# GPRS-Shield-v3_0.net
KiCad netlist of a schematic drawn in EAGLE
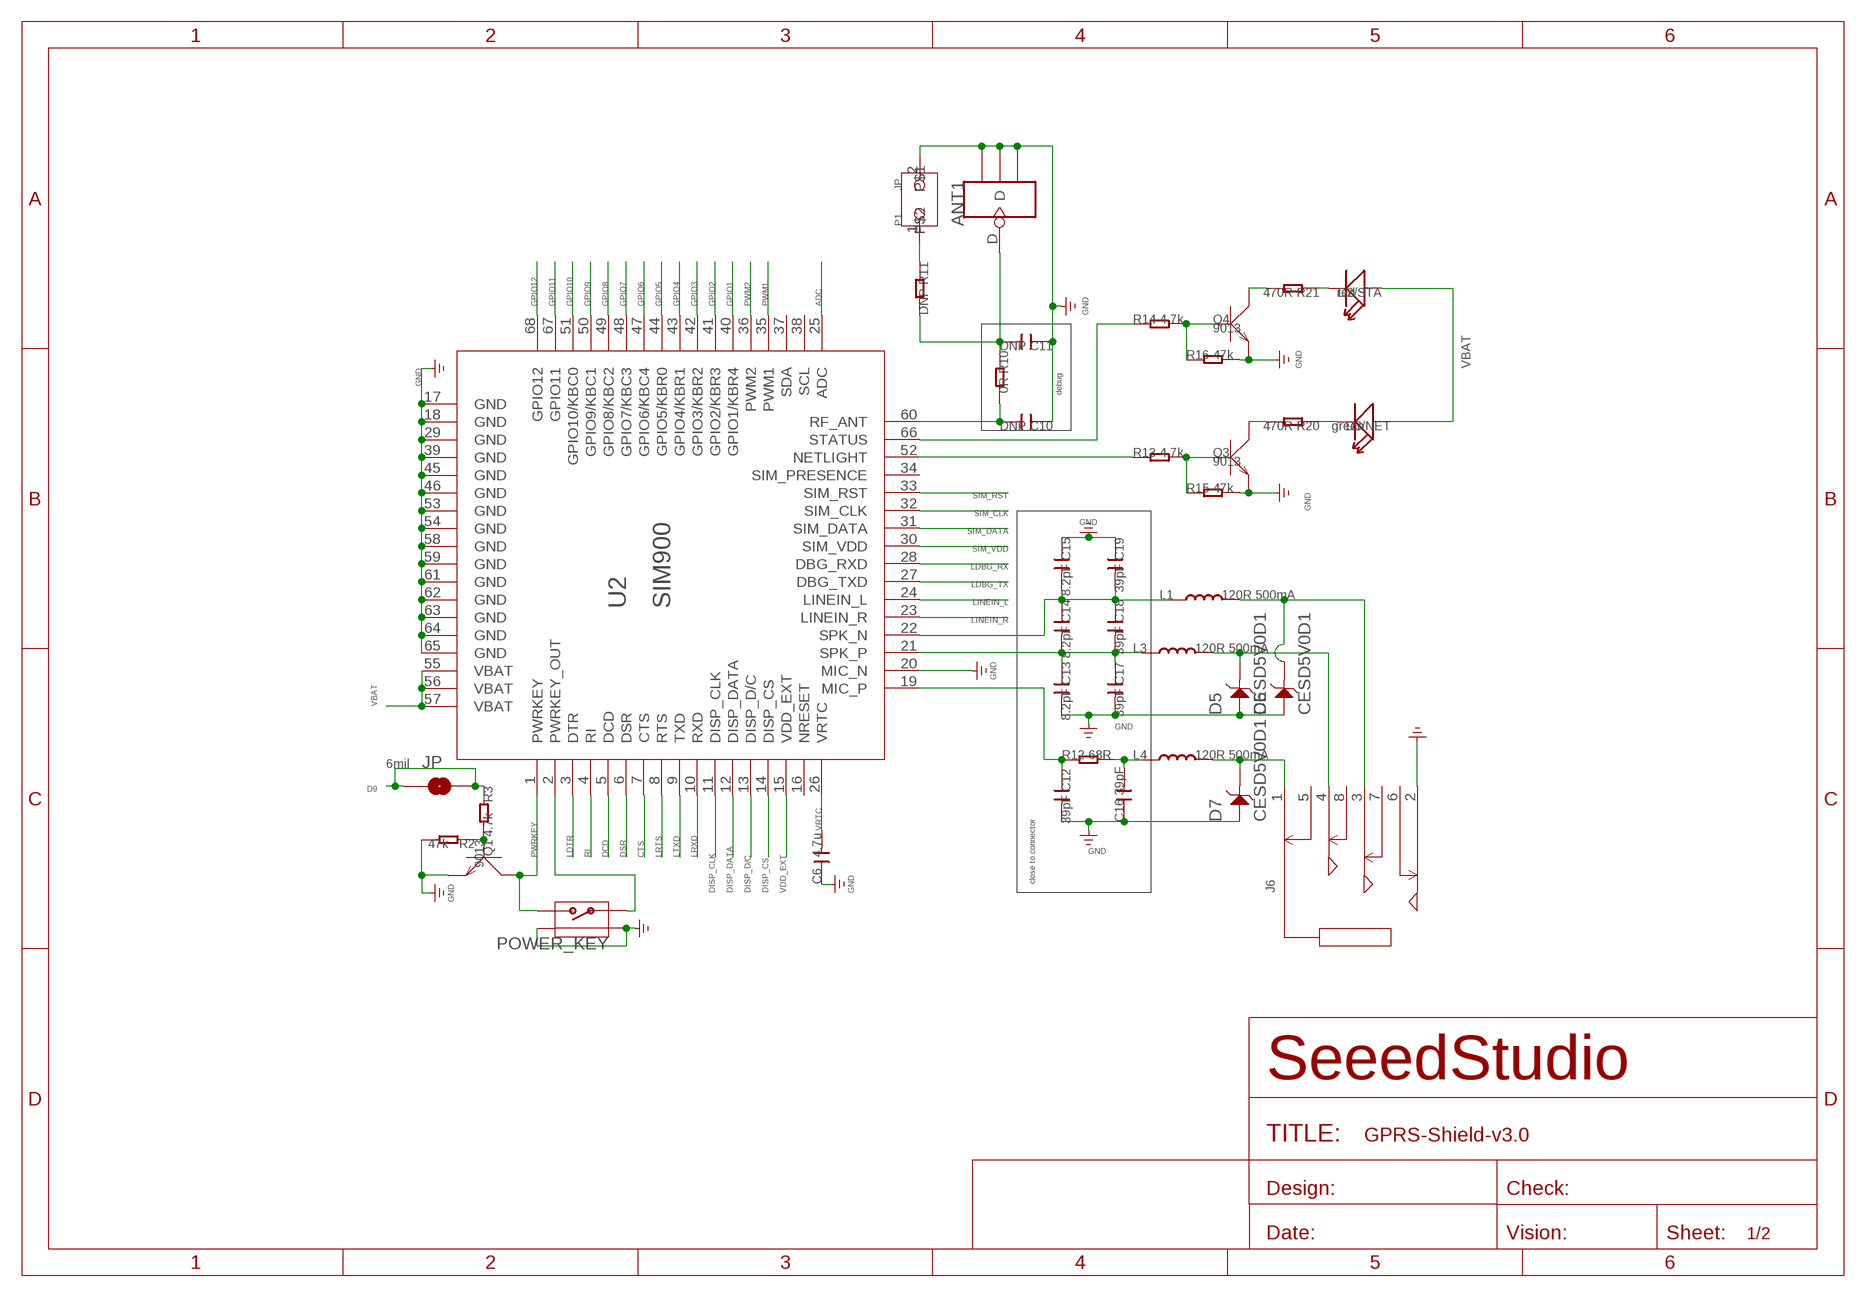
[diagram p0: schematic, sheet 1, part 1 of 2]
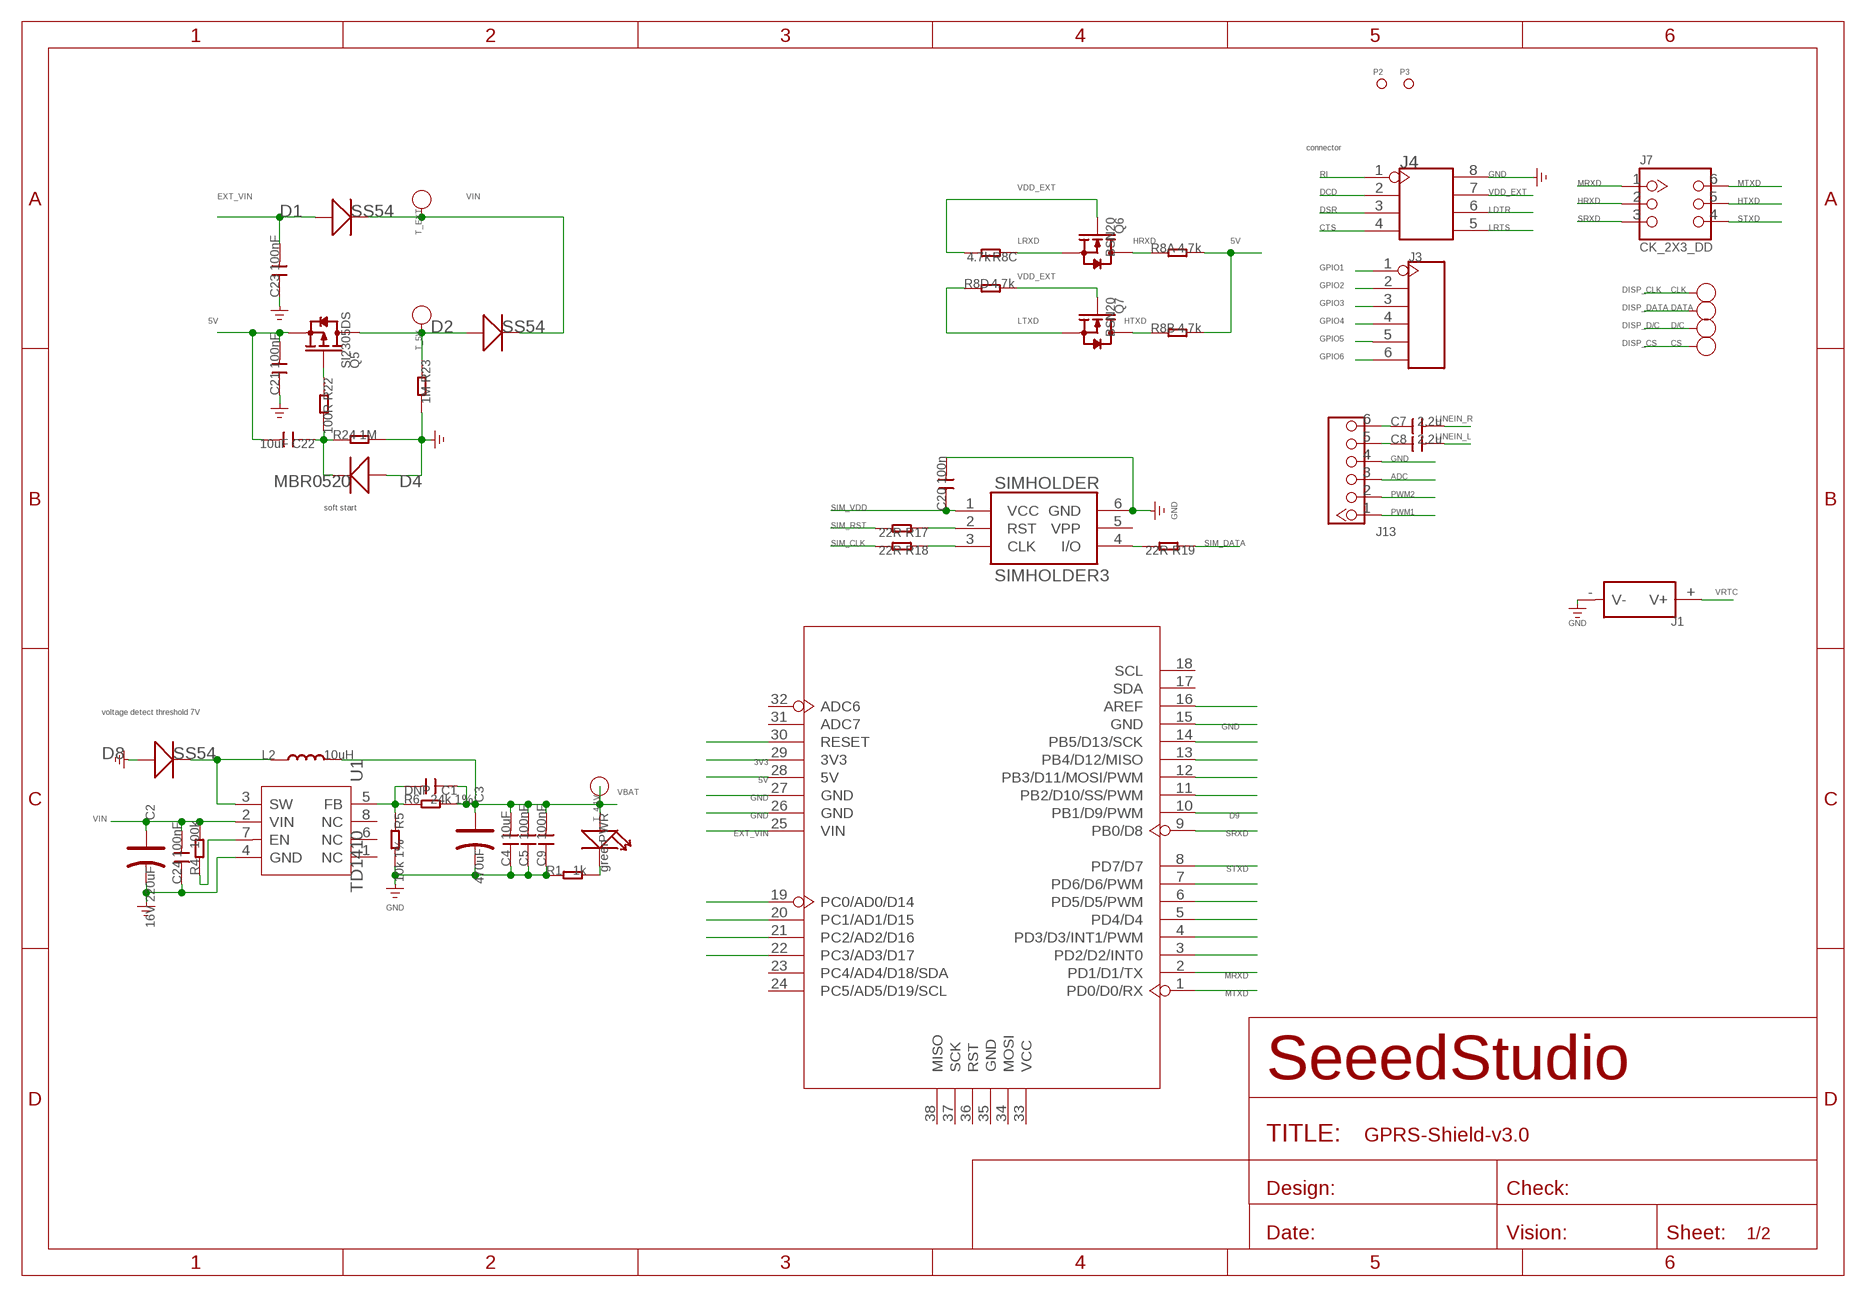
[diagram p1: schematic, sheet 1, part 2 of 2]
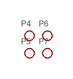
[diagram p2: schematic, sheet 2]

(export (version "E")
  (design (tool "Eeschema 10.0.6"))
  (components
    (comp (ref "P4")
      (value "PAD-MARK")
      (footprint "eagle-import:ROUND-MARK-1.0")
      (fields (field (name "PARTNO") "DNP"))
      (libsource (lib "eagle-import") (part "PAD-MARK"))
    )
    (comp (ref "P5")
      (value "PAD-MARK")
      (footprint "eagle-import:ROUND-MARK-1.0")
      (fields (field (name "PARTNO") "DNP"))
      (libsource (lib "eagle-import") (part "PAD-MARK"))
    )
    (comp (ref "P6")
      (value "PAD-MARK")
      (footprint "eagle-import:ROUND-MARK-1.0")
      (fields (field (name "PARTNO") "DNP"))
      (libsource (lib "eagle-import") (part "PAD-MARK"))
    )
    (comp (ref "P7")
      (value "PAD-MARK")
      (footprint "eagle-import:ROUND-MARK-1.0")
      (fields (field (name "PARTNO") "DNP"))
      (libsource (lib "eagle-import") (part "PAD-MARK"))
    )
    (comp (ref "ANT1")
      (value "ANTENNA-U-FL")
      (footprint "eagle-import:4P-U-FL")
      (libsource (lib "eagle-import") (part "ANTENNA-U-FL"))
    )
    (comp (ref "C1")
      (value "DNP")
      (footprint "eagle-import:C0603")
      (libsource (lib "eagle-import") (part "C-0603"))
    )
    (comp (ref "C2")
      (value "16V 220uF")
      (footprint "eagle-import:ELECTRO-SMD-D-5.6MM")
      (libsource (lib "eagle-import") (part "CAP-ELECTRO-D"))
    )
    (comp (ref "C3")
      (value "470uF")
      (footprint "eagle-import:AVX-D")
      (libsource (lib "eagle-import") (part "CAP-AVX-D"))
    )
    (comp (ref "C4")
      (value "10uF")
      (footprint "eagle-import:C0805")
      (libsource (lib "eagle-import") (part "C-0805"))
    )
    (comp (ref "C5")
      (value "100nF")
      (footprint "eagle-import:C0603")
      (libsource (lib "eagle-import") (part "C-0603"))
    )
    (comp (ref "C6")
      (value "4.7u")
      (footprint "eagle-import:C0805")
      (libsource (lib "eagle-import") (part "C-0805"))
    )
    (comp (ref "C7")
      (value "2.2u")
      (footprint "eagle-import:C0805")
      (libsource (lib "eagle-import") (part "C-0805"))
    )
    (comp (ref "C8")
      (value "2.2u")
      (footprint "eagle-import:C0805")
      (libsource (lib "eagle-import") (part "C-0805"))
    )
    (comp (ref "C9")
      (value "100nF")
      (footprint "eagle-import:C0603")
      (libsource (lib "eagle-import") (part "C-0603"))
    )
    (comp (ref "C10")
      (value "DNP")
      (footprint "eagle-import:C0603")
      (libsource (lib "eagle-import") (part "C-0603"))
    )
    (comp (ref "C11")
      (value "DNP")
      (footprint "eagle-import:C0603")
      (libsource (lib "eagle-import") (part "C-0603"))
    )
    (comp (ref "C12")
      (value "39pF")
      (footprint "eagle-import:C0603")
      (libsource (lib "eagle-import") (part "C-0603"))
    )
    (comp (ref "C13")
      (value "8.2pF")
      (footprint "eagle-import:C0603")
      (libsource (lib "eagle-import") (part "C-0603"))
    )
    (comp (ref "C14")
      (value "8.2pF")
      (footprint "eagle-import:C0603")
      (libsource (lib "eagle-import") (part "C-0603"))
    )
    (comp (ref "C15")
      (value "8.2pF")
      (footprint "eagle-import:C0603")
      (libsource (lib "eagle-import") (part "C-0603"))
    )
    (comp (ref "C16")
      (value "39pF")
      (footprint "eagle-import:C0603")
      (libsource (lib "eagle-import") (part "C-0603"))
    )
    (comp (ref "C17")
      (value "39pF")
      (footprint "eagle-import:C0603")
      (libsource (lib "eagle-import") (part "C-0603"))
    )
    (comp (ref "C18")
      (value "39pF")
      (footprint "eagle-import:C0603")
      (libsource (lib "eagle-import") (part "C-0603"))
    )
    (comp (ref "C19")
      (value "39pF")
      (footprint "eagle-import:C0603")
      (libsource (lib "eagle-import") (part "C-0603"))
    )
    (comp (ref "C20")
      (value "100n")
      (footprint "eagle-import:C0603")
      (libsource (lib "eagle-import") (part "C-0603"))
    )
    (comp (ref "C21")
      (value "100nF")
      (footprint "eagle-import:C0603")
      (libsource (lib "eagle-import") (part "C-0603"))
    )
    (comp (ref "C22")
      (value "10uF")
      (footprint "eagle-import:C0805")
      (libsource (lib "eagle-import") (part "C-0805"))
    )
    (comp (ref "C23")
      (value "100nF")
      (footprint "eagle-import:C0603")
      (libsource (lib "eagle-import") (part "C-0603"))
    )
    (comp (ref "C24")
      (value "100nF")
      (footprint "eagle-import:C0603")
      (libsource (lib "eagle-import") (part "C-0603"))
    )
    (comp (ref "CLK")
      (value "PAD-TEST-POINT-CIRCLE'4545'")
      (footprint "eagle-import:TP_4545")
      (fields (field (name "PARTNO") "DNP"))
      (libsource (lib "eagle-import") (part "PAD-TEST-POINT-CIRCLE'4545'"))
    )
    (comp (ref "CS")
      (value "PAD-TEST-POINT-CIRCLE'4545'")
      (footprint "eagle-import:TP_4545")
      (fields (field (name "PARTNO") "DNP"))
      (libsource (lib "eagle-import") (part "PAD-TEST-POINT-CIRCLE'4545'"))
    )
    (comp (ref "D/C")
      (value "PAD-TEST-POINT-CIRCLE'4545'")
      (footprint "eagle-import:TP_4545")
      (fields (field (name "PARTNO") "DNP"))
      (libsource (lib "eagle-import") (part "PAD-TEST-POINT-CIRCLE'4545'"))
    )
    (comp (ref "D1")
      (value "SS54")
      (footprint "eagle-import:SMB")
      (libsource (lib "eagle-import") (part "D'MBRS240LT3'"))
    )
    (comp (ref "D2")
      (value "SS54")
      (footprint "eagle-import:SMB")
      (libsource (lib "eagle-import") (part "D'MBRS240LT3'"))
    )
    (comp (ref "D2/STA")
      (value "red")
      (footprint "eagle-import:LED-0603")
      (libsource (lib "eagle-import") (part "LED'0603'"))
    )
    (comp (ref "D3/NET")
      (value "green")
      (footprint "eagle-import:LED-0603")
      (libsource (lib "eagle-import") (part "LED'0603'"))
    )
    (comp (ref "D4")
      (value "MBR0520")
      (footprint "eagle-import:SOD123-2.7X1.6")
      (libsource (lib "eagle-import") (part "D'MBR0520LT1'"))
    )
    (comp (ref "D5")
      (value "CESD5V0D1")
      (footprint "eagle-import:SOD123-2.7X1.6")
      (libsource (lib "eagle-import") (part "D-ESD"))
    )
    (comp (ref "D6")
      (value "CESD5V0D1")
      (footprint "eagle-import:SOD123-2.7X1.6")
      (libsource (lib "eagle-import") (part "D-ESD"))
    )
    (comp (ref "D7")
      (value "CESD5V0D1")
      (footprint "eagle-import:SOD123-2.7X1.6")
      (libsource (lib "eagle-import") (part "D-ESD"))
    )
    (comp (ref "D8")
      (value "SS54")
      (footprint "eagle-import:SMB")
      (libsource (lib "eagle-import") (part "D'MBRS240LT3'"))
    )
    (comp (ref "DATA")
      (value "PAD-TEST-POINT-CIRCLE'4545'")
      (footprint "eagle-import:TP_4545")
      (fields (field (name "PARTNO") "DNP"))
      (libsource (lib "eagle-import") (part "PAD-TEST-POINT-CIRCLE'4545'"))
    )
    (comp (ref "J1")
      (value "HOLDER-BAT")
      (footprint "eagle-import:SMD-CR1220-2")
      (libsource (lib "eagle-import") (part "HOLDER-BAT"))
    )
    (comp (ref "J3")
      (value "HEADER-6P-65/35MIL")
      (footprint "eagle-import:6P-2.54-65_35MIL")
      (libsource (lib "eagle-import") (part "HEADER-6P-65/35MIL"))
    )
    (comp (ref "J4")
      (value "HEADER-2X4P-2.54")
      (footprint "eagle-import:2X4P-2.54")
      (libsource (lib "eagle-import") (part "HEADER-2X4P-2.54"))
    )
    (comp (ref "J6")
      (value "AUDIO-JACK-3.5'PJ-393'")
      (footprint "eagle-import:8P-SMD-3.5")
      (libsource (lib "eagle-import") (part "AUDIO-JACK-3.5'PJ-393'"))
    )
    (comp (ref "J7")
      (value "CK_2X3_DD")
      (footprint "eagle-import:CK_2X3")
      (libsource (lib "eagle-import") (part "CK_2X3_DD"))
    )
    (comp (ref "J13")
      (value "HEADER_1X6")
      (footprint "eagle-import:CK_1X6")
      (libsource (lib "eagle-import") (part "HEADER_1X6"))
    )
    (comp (ref "JP")
      (value "PAD-SOLDERJUMPERNC")
      (footprint "eagle-import:2P-SMD-3.3X2")
      (libsource (lib "eagle-import") (part "PAD-SOLDERJUMPERNC"))
    )
    (comp (ref "L1")
      (value "120R 500mA")
      (footprint "eagle-import:L0603")
      (libsource (lib "eagle-import") (part "L'0603'"))
    )
    (comp (ref "L2")
      (value "10uH")
      (footprint "eagle-import:L0630")
      (libsource (lib "eagle-import") (part "L'0630'"))
    )
    (comp (ref "L3")
      (value "120R 500mA")
      (footprint "eagle-import:L0603")
      (libsource (lib "eagle-import") (part "L'0603'"))
    )
    (comp (ref "L4")
      (value "120R 500mA")
      (footprint "eagle-import:L0603")
      (libsource (lib "eagle-import") (part "L'0603'"))
    )
    (comp (ref "P1") (value "JP") (footprint "eagle-import:JP") (libsource (lib "eagle-import") (part "JP")))
    (comp (ref "P2")
      (value "PAD-MARK")
      (footprint "eagle-import:ROUND-MARK-1.0")
      (fields (field (name "PARTNO") "DNP"))
      (libsource (lib "eagle-import") (part "PAD-MARK"))
    )
    (comp (ref "P3")
      (value "PAD-MARK")
      (footprint "eagle-import:ROUND-MARK-1.0")
      (fields (field (name "PARTNO") "DNP"))
      (libsource (lib "eagle-import") (part "PAD-MARK"))
    )
    (comp (ref "POWER_KEY")
      (value "BUTTON-4P-REINFORCE'TS-118E'")
      (footprint "eagle-import:4P-SMD-7X3.5X3.5H")
      (libsource (lib "eagle-import") (part "BUTTON-4P-REINFORCE'TS-118E'"))
    )
    (comp (ref "PWR")
      (value "green")
      (footprint "eagle-import:D0603")
      (libsource (lib "eagle-import") (part "007-LED0603"))
    )
    (comp (ref "Q1")
      (value "9013")
      (footprint "eagle-import:SOT23")
      (libsource (lib "eagle-import") (part "TRANSISTOR-NPN-SOT23"))
    )
    (comp (ref "Q3")
      (value "9013")
      (footprint "eagle-import:SOT23")
      (libsource (lib "eagle-import") (part "TRANSISTOR-NPN-SOT23"))
    )
    (comp (ref "Q4")
      (value "9013")
      (footprint "eagle-import:SOT23")
      (libsource (lib "eagle-import") (part "TRANSISTOR-NPN-SOT23"))
    )
    (comp (ref "Q5")
      (value "SI2305DS")
      (footprint "eagle-import:SOT23")
      (libsource (lib "eagle-import") (part "MOSFET-P'SI2323CDS/SI2305DS{lt}BR{gt}'"))
    )
    (comp (ref "Q6")
      (value "BSN20")
      (footprint "eagle-import:SOT23")
      (libsource (lib "eagle-import") (part "MOSFET-N'SOT23'"))
    )
    (comp (ref "Q7")
      (value "BSN20")
      (footprint "eagle-import:SOT23")
      (libsource (lib "eagle-import") (part "MOSFET-N'SOT23'"))
    )
    (comp (ref "R1")
      (value "1k")
      (footprint "eagle-import:R0603")
      (libsource (lib "eagle-import") (part "R-0603"))
    )
    (comp (ref "R2")
      (value "47k")
      (footprint "eagle-import:R0603")
      (libsource (lib "eagle-import") (part "R-0603"))
    )
    (comp (ref "R3")
      (value "4.7k")
      (footprint "eagle-import:R0603")
      (libsource (lib "eagle-import") (part "R-0603"))
    )
    (comp (ref "R4")
      (value "100k")
      (footprint "eagle-import:R0603")
      (libsource (lib "eagle-import") (part "R-0603"))
    )
    (comp (ref "R5")
      (value "10k 1%")
      (footprint "eagle-import:R0603")
      (libsource (lib "eagle-import") (part "R-0603"))
    )
    (comp (ref "R6")
      (value "24k 1%")
      (footprint "eagle-import:R0603")
      (libsource (lib "eagle-import") (part "R-0603"))
    )
    (comp (ref "R8")
      (value "4.7k")
      (footprint "eagle-import:1206-8-3.3X2.4")
      (libsource (lib "eagle-import") (part "R-4R-1206"))
    )
    (comp (ref "R10")
      (value "0R")
      (footprint "eagle-import:R0603")
      (libsource (lib "eagle-import") (part "R-0603"))
    )
    (comp (ref "R11")
      (value "DNP")
      (footprint "eagle-import:R0603")
      (libsource (lib "eagle-import") (part "R-0603"))
    )
    (comp (ref "R12")
      (value "68R")
      (footprint "eagle-import:R0603")
      (libsource (lib "eagle-import") (part "R-0603"))
    )
    (comp (ref "R13")
      (value "4.7k")
      (footprint "eagle-import:R0603")
      (libsource (lib "eagle-import") (part "R-0603"))
    )
    (comp (ref "R14")
      (value "4.7k")
      (footprint "eagle-import:R0603")
      (libsource (lib "eagle-import") (part "R-0603"))
    )
    (comp (ref "R15")
      (value "47k")
      (footprint "eagle-import:R0603")
      (libsource (lib "eagle-import") (part "R-0603"))
    )
    (comp (ref "R16")
      (value "47k")
      (footprint "eagle-import:R0603")
      (libsource (lib "eagle-import") (part "R-0603"))
    )
    (comp (ref "R17")
      (value "22R")
      (footprint "eagle-import:R0603")
      (libsource (lib "eagle-import") (part "R-0603"))
    )
    (comp (ref "R18")
      (value "22R")
      (footprint "eagle-import:R0603")
      (libsource (lib "eagle-import") (part "R-0603"))
    )
    (comp (ref "R19")
      (value "22R")
      (footprint "eagle-import:R0603")
      (libsource (lib "eagle-import") (part "R-0603"))
    )
    (comp (ref "R20")
      (value "470R")
      (footprint "eagle-import:R0603")
      (libsource (lib "eagle-import") (part "R-0603"))
    )
    (comp (ref "R21")
      (value "470R")
      (footprint "eagle-import:R0603")
      (libsource (lib "eagle-import") (part "R-0603"))
    )
    (comp (ref "R22")
      (value "100R")
      (footprint "eagle-import:R0603")
      (libsource (lib "eagle-import") (part "R-0603"))
    )
    (comp (ref "R23")
      (value "1M")
      (footprint "eagle-import:R0603")
      (libsource (lib "eagle-import") (part "R-0603"))
    )
    (comp (ref "R24")
      (value "1M")
      (footprint "eagle-import:R0603")
      (libsource (lib "eagle-import") (part "R-0603"))
    )
    (comp (ref "SIMHOLDER")
      (value "SIMHOLDER3")
      (footprint "eagle-import:SIMHOLDER3")
      (libsource (lib "eagle-import") (part "SIMHOLDER3"))
    )
    (comp (ref "T_4.1V")
      (value "PAD-TEST-POINT-CIRCLE'4545'")
      (footprint "eagle-import:TP_4545")
      (fields (field (name "PARTNO") "DNP") (field (name "PARTNO_1") "DNP"))
      (libsource (lib "eagle-import") (part "PAD-TEST-POINT-CIRCLE'4545'"))
    )
    (comp (ref "T_5V")
      (value "PAD-TEST-POINT-CIRCLE'4545'")
      (footprint "eagle-import:TP_4545")
      (fields (field (name "PARTNO") "DNP") (field (name "PARTNO_1") "DNP"))
      (libsource (lib "eagle-import") (part "PAD-TEST-POINT-CIRCLE'4545'"))
    )
    (comp (ref "T_EXT")
      (value "PAD-TEST-POINT-CIRCLE'4545'")
      (footprint "eagle-import:TP_4545")
      (fields (field (name "PARTNO") "DNP") (field (name "PARTNO_1") "DNP"))
      (libsource (lib "eagle-import") (part "PAD-TEST-POINT-CIRCLE'4545'"))
    )
    (comp (ref "U1")
      (value "TD1410")
      (footprint "eagle-import:SOP8")
      (libsource (lib "eagle-import") (part "TD1410"))
    )
    (comp (ref "U2")
      (value "SIM900")
      (footprint "eagle-import:SIM900")
      (libsource (lib "eagle-import") (part "SIM900"))
    )
    (comp (ref "U4")
      (value "ARDUINO-38P'WITH/O-SILK'")
      (footprint "eagle-import:ARDUINO-38P-500519002")
      (libsource (lib "eagle-import") (part "ARDUINO-38P'WITH/O-SILK'"))
    )
  )
  (nets
    (net (code "1") (name "3V3") (class "Default")
      (node (ref "U4") (pin "29") (pinfunction "3V3_29") (pintype "bidirectional"))
    )
    (net (code "2") (name "5V") (class "Default")
      (node (ref "C21") (pin "2") (pinfunction "2_2") (pintype "passive"))
      (node (ref "C22") (pin "2") (pinfunction "2_2") (pintype "passive"))
      (node (ref "Q5") (pin "2") (pinfunction "S_2") (pintype "passive"))
      (node (ref "R8") (pin "7") (pinfunction "2_7") (pintype "passive"))
      (node (ref "R8") (pin "8") (pinfunction "2_8") (pintype "passive"))
      (node (ref "U4") (pin "28") (pinfunction "5V_28") (pintype "bidirectional"))
    )
    (net (code "3") (name "ADC") (class "Default")
      (node (ref "J13") (pin "3") (pinfunction "3_3") (pintype "bidirectional"))
      (node (ref "U2") (pin "25") (pinfunction "ADC_25") (pintype "input"))
    )
    (net (code "4") (name "CTS") (class "Default")
      (node (ref "J4") (pin "4") (pinfunction "4_4") (pintype "bidirectional"))
      (node (ref "U2") (pin "7") (pinfunction "CTS_7") (pintype "output"))
    )
    (net (code "5") (name "D9") (class "Default")
      (node (ref "JP") (pin "1") (pinfunction "1_1") (pintype "passive"))
      (node (ref "JP") (pin "2") (pinfunction "2_2") (pintype "passive"))
      (node (ref "R3") (pin "1") (pinfunction "1_1") (pintype "passive"))
      (node (ref "U4") (pin "10") (pinfunction "PB1/D9/PWM_10") (pintype "bidirectional"))
    )
    (net (code "6") (name "DCD") (class "Default")
      (node (ref "J4") (pin "2") (pinfunction "2_2") (pintype "bidirectional"))
      (node (ref "U2") (pin "5") (pinfunction "DCD_5") (pintype "output"))
    )
    (net (code "7") (name "DISP_CLK") (class "Default")
      (node (ref "CLK") (pin "T") (pinfunction "T_T") (pintype "bidirectional"))
      (node (ref "U2") (pin "11") (pinfunction "DISP_CLK_11") (pintype "output"))
    )
    (net (code "8") (name "DISP_CS") (class "Default")
      (node (ref "CS") (pin "T") (pinfunction "T_T") (pintype "bidirectional"))
      (node (ref "U2") (pin "14") (pinfunction "DISP_CS_14") (pintype "output"))
    )
    (net (code "9") (name "DISP_DATA") (class "Default")
      (node (ref "DATA") (pin "T") (pinfunction "T_T") (pintype "bidirectional"))
      (node (ref "U2") (pin "12") (pinfunction "DISP_DATA_12") (pintype "bidirectional"))
    )
    (net (code "10") (name "DISP_D{slash}C") (class "Default")
      (node (ref "D/C") (pin "T") (pinfunction "T_T") (pintype "bidirectional"))
      (node (ref "U2") (pin "13") (pinfunction "DISP_D/C_13") (pintype "output"))
    )
    (net (code "11") (name "DSR") (class "Default")
      (node (ref "J4") (pin "3") (pinfunction "3_3") (pintype "bidirectional"))
      (node (ref "U2") (pin "6") (pinfunction "DSR_6") (pintype "output"))
    )
    (net (code "12") (name "EXT_VIN") (class "Default")
      (node (ref "C23") (pin "2") (pinfunction "2_2") (pintype "passive"))
      (node (ref "D1") (pin "+") (pinfunction "+_+") (pintype "passive"))
      (node (ref "U4") (pin "25") (pinfunction "VIN_25") (pintype "bidirectional"))
    )
    (net (code "13") (name "GND") (class "Default")
      (node (ref "ANT1") (pin "GND1") (pinfunction "GND1_GND1") (pintype "bidirectional"))
      (node (ref "ANT1") (pin "GND2") (pinfunction "GND2_GND2") (pintype "bidirectional"))
      (node (ref "ANT1") (pin "GND3") (pinfunction "GND3_GND3") (pintype "bidirectional"))
      (node (ref "C10") (pin "1") (pinfunction "1_1") (pintype "passive"))
      (node (ref "C11") (pin "1") (pinfunction "1_1") (pintype "passive"))
      (node (ref "C12") (pin "2") (pinfunction "2_2") (pintype "passive"))
      (node (ref "C13") (pin "2") (pinfunction "2_2") (pintype "passive"))
      (node (ref "C15") (pin "1") (pinfunction "1_1") (pintype "passive"))
      (node (ref "C16") (pin "1") (pinfunction "1_1") (pintype "passive"))
      (node (ref "C17") (pin "2") (pinfunction "2_2") (pintype "passive"))
      (node (ref "C19") (pin "1") (pinfunction "1_1") (pintype "passive"))
      (node (ref "C2") (pin "-") (pinfunction "-_-") (pintype "passive"))
      (node (ref "C20") (pin "2") (pinfunction "2_2") (pintype "passive"))
      (node (ref "C21") (pin "1") (pinfunction "1_1") (pintype "passive"))
      (node (ref "C23") (pin "1") (pinfunction "1_1") (pintype "passive"))
      (node (ref "C24") (pin "1") (pinfunction "1_1") (pintype "passive"))
      (node (ref "C3") (pin "-") (pinfunction "-_-") (pintype "passive"))
      (node (ref "C4") (pin "1") (pinfunction "1_1") (pintype "passive"))
      (node (ref "C5") (pin "1") (pinfunction "1_1") (pintype "passive"))
      (node (ref "C6") (pin "1") (pinfunction "1_1") (pintype "passive"))
      (node (ref "C9") (pin "1") (pinfunction "1_1") (pintype "passive"))
      (node (ref "D4") (pin "1") (pinfunction "+_1") (pintype "passive"))
      (node (ref "D5") (pin "1") (pinfunction "1_1") (pintype "bidirectional"))
      (node (ref "D6") (pin "1") (pinfunction "1_1") (pintype "bidirectional"))
      (node (ref "D7") (pin "1") (pinfunction "1_1") (pintype "bidirectional"))
      (node (ref "D8") (pin "+") (pinfunction "+_+") (pintype "passive"))
      (node (ref "J1") (pin "-") (pinfunction "V-_-") (pintype "bidirectional"))
      (node (ref "J13") (pin "4") (pinfunction "4_4") (pintype "bidirectional"))
      (node (ref "J4") (pin "8") (pinfunction "8_8") (pintype "bidirectional"))
      (node (ref "J6") (pin "2") (pinfunction "2_2") (pintype "bidirectional"))
      (node (ref "P1") (pin "2") (pinfunction "P$2_2") (pintype "bidirectional"))
      (node (ref "POWER_KEY") (pin "S1") (pinfunction "S1_S1") (pintype "bidirectional"))
      (node (ref "POWER_KEY") (pin "S2") (pinfunction "S2_S2") (pintype "bidirectional"))
      (node (ref "Q1") (pin "2") (pinfunction "E_2") (pintype "passive"))
      (node (ref "Q3") (pin "2") (pinfunction "E_2") (pintype "passive"))
      (node (ref "Q4") (pin "2") (pinfunction "E_2") (pintype "passive"))
      (node (ref "R1") (pin "1") (pinfunction "1_1") (pintype "passive"))
      (node (ref "R15") (pin "2") (pinfunction "2_2") (pintype "passive"))
      (node (ref "R16") (pin "2") (pinfunction "2_2") (pintype "passive"))
      (node (ref "R2") (pin "2") (pinfunction "2_2") (pintype "passive"))
      (node (ref "R23") (pin "2") (pinfunction "2_2") (pintype "passive"))
      (node (ref "R24") (pin "2") (pinfunction "2_2") (pintype "passive"))
      (node (ref "R5") (pin "2") (pinfunction "2_2") (pintype "passive"))
      (node (ref "SIMHOLDER") (pin "6") (pinfunction "GND_6") (pintype "bidirectional"))
      (node (ref "U1") (pin "4") (pinfunction "GND_4") (pintype "power_in"))
      (node (ref "U2") (pin "17") (pinfunction "GND_17") (pintype "power_in"))
      (node (ref "U2") (pin "18") (pinfunction "GND_18") (pintype "power_in"))
      (node (ref "U2") (pin "20") (pinfunction "MIC_N_20") (pintype "input"))
      (node (ref "U2") (pin "29") (pinfunction "GND_29") (pintype "power_in"))
      (node (ref "U2") (pin "39") (pinfunction "GND_39") (pintype "power_in"))
      (node (ref "U2") (pin "45") (pinfunction "GND_45") (pintype "power_in"))
      (node (ref "U2") (pin "46") (pinfunction "GND_46") (pintype "power_in"))
      (node (ref "U2") (pin "53") (pinfunction "GND_53") (pintype "power_in"))
      (node (ref "U2") (pin "54") (pinfunction "GND_54") (pintype "power_in"))
      (node (ref "U2") (pin "58") (pinfunction "GND_58") (pintype "power_in"))
      (node (ref "U2") (pin "59") (pinfunction "GND_59") (pintype "power_in"))
      (node (ref "U2") (pin "61") (pinfunction "GND_61") (pintype "power_in"))
      (node (ref "U2") (pin "62") (pinfunction "GND_62") (pintype "power_in"))
      (node (ref "U2") (pin "63") (pinfunction "GND_63") (pintype "power_in"))
      (node (ref "U2") (pin "64") (pinfunction "GND_64") (pintype "power_in"))
      (node (ref "U2") (pin "65") (pinfunction "GND_65") (pintype "power_in"))
      (node (ref "U4") (pin "15") (pinfunction "GND_15") (pintype "bidirectional"))
      (node (ref "U4") (pin "26") (pinfunction "GND_26") (pintype "bidirectional"))
      (node (ref "U4") (pin "27") (pinfunction "GND_27") (pintype "bidirectional"))
    )
    (net (code "14") (name "GPIO1") (class "Default")
      (node (ref "J3") (pin "1") (pinfunction "1_1") (pintype "bidirectional"))
      (node (ref "U2") (pin "40") (pinfunction "GPIO1/KBR4_40") (pintype "output"))
    )
    (net (code "15") (name "GPIO2") (class "Default")
      (node (ref "J3") (pin "2") (pinfunction "2_2") (pintype "bidirectional"))
      (node (ref "U2") (pin "41") (pinfunction "GPIO2/KBR3_41") (pintype "output"))
    )
    (net (code "16") (name "GPIO3") (class "Default")
      (node (ref "J3") (pin "3") (pinfunction "3_3") (pintype "bidirectional"))
      (node (ref "U2") (pin "42") (pinfunction "GPIO3/KBR2_42") (pintype "output"))
    )
    (net (code "17") (name "GPIO4") (class "Default")
      (node (ref "J3") (pin "4") (pinfunction "4_4") (pintype "bidirectional"))
      (node (ref "U2") (pin "43") (pinfunction "GPIO4/KBR1_43") (pintype "output"))
    )
    (net (code "18") (name "GPIO5") (class "Default")
      (node (ref "J3") (pin "5") (pinfunction "5_5") (pintype "bidirectional"))
      (node (ref "U2") (pin "44") (pinfunction "GPIO5/KBR0_44") (pintype "output"))
    )
    (net (code "19") (name "GPIO6") (class "Default")
      (node (ref "J3") (pin "6") (pinfunction "6_6") (pintype "bidirectional"))
      (node (ref "U2") (pin "47") (pinfunction "GPIO6/KBC4_47") (pintype "input"))
    )
    (net (code "20") (name "GPIO7") (class "Default")
      (node (ref "U2") (pin "48") (pinfunction "GPIO7/KBC3_48") (pintype "bidirectional"))
    )
    (net (code "21") (name "GPIO8") (class "Default")
      (node (ref "U2") (pin "49") (pinfunction "GPIO8/KBC2_49") (pintype "input"))
    )
    (net (code "22") (name "GPIO9") (class "Default")
      (node (ref "U2") (pin "50") (pinfunction "GPIO9/KBC1_50") (pintype "input"))
    )
    (net (code "23") (name "GPIO10") (class "Default")
      (node (ref "U2") (pin "51") (pinfunction "GPIO10/KBC0_51") (pintype "bidirectional"))
    )
    (net (code "24") (name "GPIO11") (class "Default")
      (node (ref "U2") (pin "67") (pinfunction "GPIO11_67") (pintype "bidirectional"))
    )
    (net (code "25") (name "GPIO12") (class "Default")
      (node (ref "U2") (pin "68") (pinfunction "GPIO12_68") (pintype "bidirectional"))
    )
    (net (code "26") (name "HRXD") (class "Default")
      (node (ref "J7") (pin "2") (pinfunction "2_2") (pintype "bidirectional"))
      (node (ref "Q6") (pin "3") (pinfunction "D_3") (pintype "passive"))
      (node (ref "R8") (pin "1") (pinfunction "1_1") (pintype "passive"))
    )
    (net (code "27") (name "HTXD") (class "Default")
      (node (ref "J7") (pin "5") (pinfunction "5_5") (pintype "bidirectional"))
      (node (ref "Q7") (pin "3") (pinfunction "D_3") (pintype "passive"))
      (node (ref "R8") (pin "2") (pinfunction "1_2") (pintype "passive"))
    )
    (net (code "28") (name "LDBG_RX") (class "Default")
      (node (ref "U2") (pin "28") (pinfunction "DBG_RXD_28") (pintype "input"))
    )
    (net (code "29") (name "LDBG_TX") (class "Default")
      (node (ref "U2") (pin "27") (pinfunction "DBG_TXD_27") (pintype "output"))
    )
    (net (code "30") (name "LDTR") (class "Default")
      (node (ref "J4") (pin "6") (pinfunction "6_6") (pintype "bidirectional"))
      (node (ref "U2") (pin "3") (pinfunction "DTR_3") (pintype "input"))
    )
    (net (code "31") (name "LINEIN_L") (class "Default")
      (node (ref "C8") (pin "2") (pinfunction "2_2") (pintype "passive"))
      (node (ref "U2") (pin "24") (pinfunction "LINEIN_L_24") (pintype "input"))
    )
    (net (code "32") (name "LINEIN_R") (class "Default")
      (node (ref "C7") (pin "2") (pinfunction "2_2") (pintype "passive"))
      (node (ref "U2") (pin "23") (pinfunction "LINEIN_R_23") (pintype "input"))
    )
    (net (code "33") (name "LRTS") (class "Default")
      (node (ref "J4") (pin "5") (pinfunction "5_5") (pintype "bidirectional"))
      (node (ref "U2") (pin "8") (pinfunction "RTS_8") (pintype "input"))
    )
    (net (code "34") (name "LRXD") (class "Default")
      (node (ref "Q6") (pin "2") (pinfunction "S_2") (pintype "passive"))
      (node (ref "R8") (pin "3") (pinfunction "1_3") (pintype "passive"))
      (node (ref "U2") (pin "10") (pinfunction "RXD_10") (pintype "input"))
    )
    (net (code "35") (name "LTXD") (class "Default")
      (node (ref "Q7") (pin "2") (pinfunction "S_2") (pintype "passive"))
      (node (ref "R8") (pin "4") (pinfunction "1_4") (pintype "passive"))
      (node (ref "U2") (pin "9") (pinfunction "TXD_9") (pintype "output"))
    )
    (net (code "36") (name "MRXD") (class "Default")
      (node (ref "J7") (pin "1") (pinfunction "1_1") (pintype "bidirectional"))
      (node (ref "U4") (pin "2") (pinfunction "PD1/D1/TX_2") (pintype "bidirectional"))
    )
    (net (code "37") (name "MTXD") (class "Default")
      (node (ref "J7") (pin "6") (pinfunction "6_6") (pintype "bidirectional"))
      (node (ref "U4") (pin "1") (pinfunction "PD0/D0/RX_1") (pintype "bidirectional"))
    )
    (net (code "38") (name "Net-(ANT1-PadD)") (class "Default")
      (node (ref "ANT1") (pin "D") (pinfunction "D_D") (pintype "bidirectional"))
      (node (ref "C11") (pin "2") (pinfunction "2_2") (pintype "passive"))
      (node (ref "R10") (pin "1") (pinfunction "1_1") (pintype "passive"))
      (node (ref "R11") (pin "2") (pinfunction "2_2") (pintype "passive"))
    )
    (net (code "39") (name "Net-(C7-Pad1)") (class "Default")
      (node (ref "C7") (pin "1") (pinfunction "1_1") (pintype "passive"))
      (node (ref "J13") (pin "6") (pinfunction "6_6") (pintype "bidirectional"))
    )
    (net (code "40") (name "Net-(C8-Pad1)") (class "Default")
      (node (ref "C8") (pin "1") (pinfunction "1_1") (pintype "passive"))
      (node (ref "J13") (pin "5") (pinfunction "5_5") (pintype "bidirectional"))
    )
    (net (code "41") (name "Net-(C16-Pad2)") (class "Default")
      (node (ref "C16") (pin "2") (pinfunction "2_2") (pintype "passive"))
      (node (ref "L4") (pin "1") (pinfunction "1_1") (pintype "passive"))
      (node (ref "R12") (pin "2") (pinfunction "2_2") (pintype "passive"))
    )
    (net (code "42") (name "Net-(D2/STA-Pad-)") (class "Default")
      (node (ref "D2/STA") (pin "-") (pinfunction "-_-") (pintype "passive"))
      (node (ref "R21") (pin "1") (pinfunction "1_1") (pintype "passive"))
    )
    (net (code "43") (name "Net-(D3/NET-Pad-)") (class "Default")
      (node (ref "D3/NET") (pin "-") (pinfunction "-_-") (pintype "passive"))
      (node (ref "R20") (pin "1") (pinfunction "1_1") (pintype "passive"))
    )
    (net (code "44") (name "Net-(D4--)") (class "Default")
      (node (ref "C22") (pin "1") (pinfunction "1_1") (pintype "passive"))
      (node (ref "D4") (pin "2") (pinfunction "-_2") (pintype "passive"))
      (node (ref "R22") (pin "2") (pinfunction "2_2") (pintype "passive"))
      (node (ref "R24") (pin "1") (pinfunction "1_1") (pintype "passive"))
    )
    (net (code "45") (name "Net-(D5-Pad2)") (class "Default")
      (node (ref "D5") (pin "2") (pinfunction "2_2") (pintype "bidirectional"))
      (node (ref "J6") (pin "4") (pinfunction "4_4") (pintype "bidirectional"))
      (node (ref "L3") (pin "2") (pinfunction "2_2") (pintype "passive"))
    )
    (net (code "46") (name "Net-(D6-Pad2)") (class "Default")
      (node (ref "D6") (pin "2") (pinfunction "2_2") (pintype "bidirectional"))
      (node (ref "J6") (pin "3") (pinfunction "3_3") (pintype "bidirectional"))
      (node (ref "L1") (pin "2") (pinfunction "2_2") (pintype "passive"))
    )
    (net (code "47") (name "Net-(D7-Pad2)") (class "Default")
      (node (ref "D7") (pin "2") (pinfunction "2_2") (pintype "bidirectional"))
      (node (ref "J6") (pin "1") (pinfunction "1_1") (pintype "bidirectional"))
      (node (ref "L4") (pin "2") (pinfunction "2_2") (pintype "passive"))
    )
    (net (code "48") (name "Net-(P1-P$1)") (class "Default")
      (node (ref "P1") (pin "1") (pinfunction "P$1_1") (pintype "bidirectional"))
      (node (ref "R11") (pin "1") (pinfunction "1_1") (pintype "passive"))
    )
    (net (code "49") (name "Net-(PWR-Pad-)") (class "Default")
      (node (ref "PWR") (pin "-") (pinfunction "-_-") (pintype "passive"))
      (node (ref "R1") (pin "2") (pinfunction "2_2") (pintype "passive"))
    )
    (net (code "50") (name "Net-(Q1-B)") (class "Default")
      (node (ref "Q1") (pin "1") (pinfunction "B_1") (pintype "passive"))
      (node (ref "R2") (pin "1") (pinfunction "1_1") (pintype "passive"))
      (node (ref "R3") (pin "2") (pinfunction "2_2") (pintype "passive"))
    )
    (net (code "51") (name "Net-(Q3-B)") (class "Default")
      (node (ref "Q3") (pin "1") (pinfunction "B_1") (pintype "passive"))
      (node (ref "R13") (pin "2") (pinfunction "2_2") (pintype "passive"))
      (node (ref "R15") (pin "1") (pinfunction "1_1") (pintype "passive"))
    )
    (net (code "52") (name "Net-(Q3-C)") (class "Default")
      (node (ref "Q3") (pin "3") (pinfunction "C_3") (pintype "passive"))
      (node (ref "R20") (pin "2") (pinfunction "2_2") (pintype "passive"))
    )
    (net (code "53") (name "Net-(Q4-B)") (class "Default")
      (node (ref "Q4") (pin "1") (pinfunction "B_1") (pintype "passive"))
      (node (ref "R14") (pin "2") (pinfunction "2_2") (pintype "passive"))
      (node (ref "R16") (pin "1") (pinfunction "1_1") (pintype "passive"))
    )
    (net (code "54") (name "Net-(Q4-C)") (class "Default")
      (node (ref "Q4") (pin "3") (pinfunction "C_3") (pintype "passive"))
      (node (ref "R21") (pin "2") (pinfunction "2_2") (pintype "passive"))
    )
    (net (code "55") (name "Net-(Q5-D)") (class "Default")
      (node (ref "D2") (pin "+") (pinfunction "+_+") (pintype "passive"))
      (node (ref "Q5") (pin "3") (pinfunction "D_3") (pintype "passive"))
      (node (ref "R23") (pin "1") (pinfunction "1_1") (pintype "passive"))
      (node (ref "T_5V") (pin "T") (pinfunction "T_T") (pintype "bidirectional"))
    )
    (net (code "56") (name "Net-(Q5-G)") (class "Default")
      (node (ref "Q5") (pin "1") (pinfunction "G_1") (pintype "passive"))
      (node (ref "R22") (pin "1") (pinfunction "1_1") (pintype "passive"))
    )
    (net (code "57") (name "Net-(SIMHOLDER-CLK)") (class "Default")
      (node (ref "R18") (pin "1") (pinfunction "1_1") (pintype "passive"))
      (node (ref "SIMHOLDER") (pin "3") (pinfunction "CLK_3") (pintype "bidirectional"))
    )
    (net (code "58") (name "Net-(SIMHOLDER-I{slash}O)") (class "Default")
      (node (ref "R19") (pin "2") (pinfunction "2_2") (pintype "passive"))
      (node (ref "SIMHOLDER") (pin "4") (pinfunction "I/O_4") (pintype "bidirectional"))
    )
    (net (code "59") (name "Net-(SIMHOLDER-RST)") (class "Default")
      (node (ref "R17") (pin "1") (pinfunction "1_1") (pintype "passive"))
      (node (ref "SIMHOLDER") (pin "2") (pinfunction "RST_2") (pintype "bidirectional"))
    )
    (net (code "60") (name "Net-(U1-EN)") (class "Default")
      (node (ref "R4") (pin "1") (pinfunction "1_1") (pintype "passive"))
      (node (ref "U1") (pin "7") (pinfunction "EN_7") (pintype "input"))
    )
    (net (code "61") (name "Net-(U1-FB)") (class "Default")
      (node (ref "C1") (pin "2") (pinfunction "2_2") (pintype "passive"))
      (node (ref "R5") (pin "1") (pinfunction "1_1") (pintype "passive"))
      (node (ref "R6") (pin "1") (pinfunction "1_1") (pintype "passive"))
      (node (ref "U1") (pin "5") (pinfunction "FB_5") (pintype "input"))
    )
    (net (code "62") (name "Net-(U1-SW)") (class "Default")
      (node (ref "D8") (pin "-") (pinfunction "-_-") (pintype "passive"))
      (node (ref "L2") (pin "1") (pinfunction "1_1") (pintype "passive"))
      (node (ref "U1") (pin "3") (pinfunction "SW_3") (pintype "output"))
    )
    (net (code "63") (name "Net-(U2-MIC_P)") (class "Default")
      (node (ref "C12") (pin "1") (pinfunction "1_1") (pintype "passive"))
      (node (ref "R12") (pin "1") (pinfunction "1_1") (pintype "passive"))
      (node (ref "U2") (pin "19") (pinfunction "MIC_P_19") (pintype "input"))
    )
    (net (code "64") (name "Net-(U2-NETLIGHT)") (class "Default")
      (node (ref "R13") (pin "1") (pinfunction "1_1") (pintype "passive"))
      (node (ref "U2") (pin "52") (pinfunction "NETLIGHT_52") (pintype "output"))
    )
    (net (code "65") (name "Net-(U2-PWRKEY_OUT)") (class "Default")
      (node (ref "POWER_KEY") (pin "1") (pinfunction "1_1") (pintype "bidirectional"))
      (node (ref "U2") (pin "2") (pinfunction "PWRKEY_OUT_2") (pintype "output"))
    )
    (net (code "66") (name "Net-(U2-RF_ANT)") (class "Default")
      (node (ref "C10") (pin "2") (pinfunction "2_2") (pintype "passive"))
      (node (ref "R10") (pin "2") (pinfunction "2_2") (pintype "passive"))
      (node (ref "U2") (pin "60") (pinfunction "RF_ANT_60") (pintype "bidirectional"))
    )
    (net (code "67") (name "Net-(U2-SPK_N)") (class "Default")
      (node (ref "C14") (pin "1") (pinfunction "1_1") (pintype "passive"))
      (node (ref "C15") (pin "2") (pinfunction "2_2") (pintype "passive"))
      (node (ref "C18") (pin "1") (pinfunction "1_1") (pintype "passive"))
      (node (ref "C19") (pin "2") (pinfunction "2_2") (pintype "passive"))
      (node (ref "L1") (pin "1") (pinfunction "1_1") (pintype "passive"))
      (node (ref "U2") (pin "22") (pinfunction "SPK_N_22") (pintype "output"))
    )
    (net (code "68") (name "Net-(U2-SPK_P)") (class "Default")
      (node (ref "C13") (pin "1") (pinfunction "1_1") (pintype "passive"))
      (node (ref "C14") (pin "2") (pinfunction "2_2") (pintype "passive"))
      (node (ref "C17") (pin "1") (pinfunction "1_1") (pintype "passive"))
      (node (ref "C18") (pin "2") (pinfunction "2_2") (pintype "passive"))
      (node (ref "L3") (pin "1") (pinfunction "1_1") (pintype "passive"))
      (node (ref "U2") (pin "21") (pinfunction "SPK_P_21") (pintype "output"))
    )
    (net (code "69") (name "Net-(U2-STATUS)") (class "Default")
      (node (ref "R14") (pin "1") (pinfunction "1_1") (pintype "passive"))
      (node (ref "U2") (pin "66") (pinfunction "STATUS_66") (pintype "output"))
    )
    (net (code "70") (name "PWM1") (class "Default")
      (node (ref "J13") (pin "1") (pinfunction "1_1") (pintype "bidirectional"))
      (node (ref "U2") (pin "35") (pinfunction "PWM1_35") (pintype "output"))
    )
    (net (code "71") (name "PWM2") (class "Default")
      (node (ref "J13") (pin "2") (pinfunction "2_2") (pintype "bidirectional"))
      (node (ref "U2") (pin "36") (pinfunction "PWM2_36") (pintype "output"))
    )
    (net (code "72") (name "PWRKEY") (class "Default")
      (node (ref "POWER_KEY") (pin "2") (pinfunction "2_2") (pintype "bidirectional"))
      (node (ref "Q1") (pin "3") (pinfunction "C_3") (pintype "passive"))
      (node (ref "U2") (pin "1") (pinfunction "PWRKEY_1") (pintype "input"))
    )
    (net (code "73") (name "RI") (class "Default")
      (node (ref "J4") (pin "1") (pinfunction "1_1") (pintype "bidirectional"))
      (node (ref "U2") (pin "4") (pinfunction "RI_4") (pintype "output"))
    )
    (net (code "74") (name "SIM_CLK") (class "Default")
      (node (ref "R18") (pin "2") (pinfunction "2_2") (pintype "passive"))
      (node (ref "U2") (pin "32") (pinfunction "SIM_CLK_32") (pintype "output"))
    )
    (net (code "75") (name "SIM_DATA") (class "Default")
      (node (ref "R19") (pin "1") (pinfunction "1_1") (pintype "passive"))
      (node (ref "U2") (pin "31") (pinfunction "SIM_DATA_31") (pintype "bidirectional"))
    )
    (net (code "76") (name "SIM_RST") (class "Default")
      (node (ref "R17") (pin "2") (pinfunction "2_2") (pintype "passive"))
      (node (ref "U2") (pin "33") (pinfunction "SIM_RST_33") (pintype "output"))
    )
    (net (code "77") (name "SIM_VDD") (class "Default")
      (node (ref "C20") (pin "1") (pinfunction "1_1") (pintype "passive"))
      (node (ref "SIMHOLDER") (pin "1") (pinfunction "VCC_1") (pintype "bidirectional"))
      (node (ref "U2") (pin "30") (pinfunction "SIM_VDD_30") (pintype "output"))
    )
    (net (code "78") (name "SRXD") (class "Default")
      (node (ref "J7") (pin "3") (pinfunction "3_3") (pintype "bidirectional"))
      (node (ref "U4") (pin "9") (pinfunction "PB0/D8_9") (pintype "bidirectional"))
    )
    (net (code "79") (name "STXD") (class "Default")
      (node (ref "J7") (pin "4") (pinfunction "4_4") (pintype "bidirectional"))
      (node (ref "U4") (pin "8") (pinfunction "PD7/D7_8") (pintype "bidirectional"))
    )
    (net (code "80") (name "VBAT") (class "Default")
      (node (ref "C1") (pin "1") (pinfunction "1_1") (pintype "passive"))
      (node (ref "C3") (pin "+") (pinfunction "+_+") (pintype "passive"))
      (node (ref "C4") (pin "2") (pinfunction "2_2") (pintype "passive"))
      (node (ref "C5") (pin "2") (pinfunction "2_2") (pintype "passive"))
      (node (ref "C9") (pin "2") (pinfunction "2_2") (pintype "passive"))
      (node (ref "D2/STA") (pin "+") (pinfunction "+_+") (pintype "passive"))
      (node (ref "D3/NET") (pin "+") (pinfunction "+_+") (pintype "passive"))
      (node (ref "L2") (pin "2") (pinfunction "2_2") (pintype "passive"))
      (node (ref "PWR") (pin "+") (pinfunction "+_+") (pintype "passive"))
      (node (ref "R6") (pin "2") (pinfunction "2_2") (pintype "passive"))
      (node (ref "T_4.1V") (pin "T") (pinfunction "T_T") (pintype "bidirectional"))
      (node (ref "U2") (pin "55") (pinfunction "VBAT_55") (pintype "power_in"))
      (node (ref "U2") (pin "56") (pinfunction "VBAT_56") (pintype "power_in"))
      (node (ref "U2") (pin "57") (pinfunction "VBAT_57") (pintype "power_in"))
    )
    (net (code "81") (name "VDD_EXT") (class "Default")
      (node (ref "J4") (pin "7") (pinfunction "7_7") (pintype "bidirectional"))
      (node (ref "Q6") (pin "1") (pinfunction "G_1") (pintype "passive"))
      (node (ref "Q7") (pin "1") (pinfunction "G_1") (pintype "passive"))
      (node (ref "R8") (pin "5") (pinfunction "2_5") (pintype "passive"))
      (node (ref "R8") (pin "6") (pinfunction "2_6") (pintype "passive"))
      (node (ref "U2") (pin "15") (pinfunction "VDD_EXT_15") (pintype "output"))
    )
    (net (code "82") (name "VIN") (class "Default")
      (node (ref "C2") (pin "+") (pinfunction "+_+") (pintype "passive"))
      (node (ref "C24") (pin "2") (pinfunction "2_2") (pintype "passive"))
      (node (ref "D1") (pin "-") (pinfunction "-_-") (pintype "passive"))
      (node (ref "D2") (pin "-") (pinfunction "-_-") (pintype "passive"))
      (node (ref "R4") (pin "2") (pinfunction "2_2") (pintype "passive"))
      (node (ref "T_EXT") (pin "T") (pinfunction "T_T") (pintype "bidirectional"))
      (node (ref "U1") (pin "2") (pinfunction "VIN_2") (pintype "input"))
    )
    (net (code "83") (name "VRTC") (class "Default")
      (node (ref "C6") (pin "2") (pinfunction "2_2") (pintype "passive"))
      (node (ref "J1") (pin "+") (pinfunction "V+_+") (pintype "bidirectional"))
      (node (ref "U2") (pin "26") (pinfunction "VRTC_26") (pintype "bidirectional"))
    )
    (net (code "84") (name "unconnected-(J6-Pad5)") (class "Default")
      (node (ref "J6") (pin "5") (pinfunction "5_5") (pintype "bidirectional"))
    )
    (net (code "85") (name "unconnected-(J6-Pad6)") (class "Default")
      (node (ref "J6") (pin "6") (pinfunction "6_6") (pintype "bidirectional"))
    )
    (net (code "86") (name "unconnected-(J6-Pad7)") (class "Default")
      (node (ref "J6") (pin "7") (pinfunction "7_7") (pintype "bidirectional"))
    )
    (net (code "87") (name "unconnected-(J6-Pad8)") (class "Default")
      (node (ref "J6") (pin "8") (pinfunction "8_8") (pintype "bidirectional"))
    )
    (net (code "88") (name "unconnected-(SIMHOLDER-VPP-Pad5)") (class "Default")
      (node (ref "SIMHOLDER") (pin "5") (pinfunction "VPP_5") (pintype "bidirectional"))
    )
    (net (code "89") (name "unconnected-(U1-NC-Pad1)") (class "Default")
      (node (ref "U1") (pin "1") (pinfunction "NC_1") (pintype "no_connect"))
    )
    (net (code "90") (name "unconnected-(U1-NC-Pad6)") (class "Default")
      (node (ref "U1") (pin "6") (pinfunction "NC_6") (pintype "no_connect"))
    )
    (net (code "91") (name "unconnected-(U1-NC-Pad8)") (class "Default")
      (node (ref "U1") (pin "8") (pinfunction "NC_8") (pintype "no_connect"))
    )
    (net (code "92") (name "unconnected-(U2-NRESET-Pad16)") (class "Default")
      (node (ref "U2") (pin "16") (pinfunction "NRESET_16") (pintype "input"))
    )
    (net (code "93") (name "unconnected-(U2-SCL-Pad38)") (class "Default")
      (node (ref "U2") (pin "38") (pinfunction "SCL_38") (pintype "output"))
    )
    (net (code "94") (name "unconnected-(U2-SDA-Pad37)") (class "Default")
      (node (ref "U2") (pin "37") (pinfunction "SDA_37") (pintype "bidirectional"))
    )
    (net (code "95") (name "unconnected-(U2-SIM_PRESENCE-Pad34)") (class "Default")
      (node (ref "U2") (pin "34") (pinfunction "SIM_PRESENCE_34") (pintype "input"))
    )
    (net (code "96") (name "unconnected-(U4-ADC6-Pad32)") (class "Default")
      (node (ref "U4") (pin "32") (pinfunction "ADC6_32") (pintype "bidirectional"))
    )
    (net (code "97") (name "unconnected-(U4-ADC7-Pad31)") (class "Default")
      (node (ref "U4") (pin "31") (pinfunction "ADC7_31") (pintype "bidirectional"))
    )
    (net (code "98") (name "unconnected-(U4-AREF-Pad16)") (class "Default")
      (node (ref "U4") (pin "16") (pinfunction "AREF_16") (pintype "bidirectional"))
    )
    (net (code "99") (name "unconnected-(U4-GND-Pad35)") (class "Default")
      (node (ref "U4") (pin "35") (pinfunction "GND_35") (pintype "bidirectional"))
    )
    (net (code "100") (name "unconnected-(U4-MISO-Pad38)") (class "Default")
      (node (ref "U4") (pin "38") (pinfunction "MISO_38") (pintype "bidirectional"))
    )
    (net (code "101") (name "unconnected-(U4-MOSI-Pad34)") (class "Default")
      (node (ref "U4") (pin "34") (pinfunction "MOSI_34") (pintype "bidirectional"))
    )
    (net (code "102") (name "unconnected-(U4-PB2{slash}D10{slash}SS{slash}PWM-Pad11)") (class "Default")
      (node (ref "U4") (pin "11") (pinfunction "PB2/D10/SS/PWM_11") (pintype "bidirectional"))
    )
    (net (code "103") (name "unconnected-(U4-PB3{slash}D11{slash}MOSI{slash}PWM-Pad12)") (class "Default")
      (node (ref "U4") (pin "12") (pinfunction "PB3/D11/MOSI/PWM_12") (pintype "bidirectional"))
    )
    (net (code "104") (name "unconnected-(U4-PB4{slash}D12{slash}MISO-Pad13)") (class "Default")
      (node (ref "U4") (pin "13") (pinfunction "PB4/D12/MISO_13") (pintype "bidirectional"))
    )
    (net (code "105") (name "unconnected-(U4-PB5{slash}D13{slash}SCK-Pad14)") (class "Default")
      (node (ref "U4") (pin "14") (pinfunction "PB5/D13/SCK_14") (pintype "bidirectional"))
    )
    (net (code "106") (name "unconnected-(U4-PC0{slash}AD0{slash}D14-Pad19)") (class "Default")
      (node (ref "U4") (pin "19") (pinfunction "PC0/AD0/D14_19") (pintype "bidirectional"))
    )
    (net (code "107") (name "unconnected-(U4-PC1{slash}AD1{slash}D15-Pad20)") (class "Default")
      (node (ref "U4") (pin "20") (pinfunction "PC1/AD1/D15_20") (pintype "bidirectional"))
    )
    (net (code "108") (name "unconnected-(U4-PC2{slash}AD2{slash}D16-Pad21)") (class "Default")
      (node (ref "U4") (pin "21") (pinfunction "PC2/AD2/D16_21") (pintype "bidirectional"))
    )
    (net (code "109") (name "unconnected-(U4-PC3{slash}AD3{slash}D17-Pad22)") (class "Default")
      (node (ref "U4") (pin "22") (pinfunction "PC3/AD3/D17_22") (pintype "bidirectional"))
    )
    (net (code "110") (name "unconnected-(U4-PC4{slash}AD4{slash}D18{slash}SDA-Pad23)") (class "Default")
      (node (ref "U4") (pin "23") (pinfunction "PC4/AD4/D18/SDA_23") (pintype "bidirectional"))
    )
    (net (code "111") (name "unconnected-(U4-PC5{slash}AD5{slash}D19{slash}SCL-Pad24)") (class "Default")
      (node (ref "U4") (pin "24") (pinfunction "PC5/AD5/D19/SCL_24") (pintype "bidirectional"))
    )
    (net (code "112") (name "unconnected-(U4-PD2{slash}D2{slash}INT0-Pad3)") (class "Default")
      (node (ref "U4") (pin "3") (pinfunction "PD2/D2/INT0_3") (pintype "bidirectional"))
    )
    (net (code "113") (name "unconnected-(U4-PD3{slash}D3{slash}INT1{slash}PWM-Pad4)") (class "Default")
      (node (ref "U4") (pin "4") (pinfunction "PD3/D3/INT1/PWM_4") (pintype "bidirectional"))
    )
    (net (code "114") (name "unconnected-(U4-PD4{slash}D4-Pad5)") (class "Default")
      (node (ref "U4") (pin "5") (pinfunction "PD4/D4_5") (pintype "bidirectional"))
    )
    (net (code "115") (name "unconnected-(U4-PD5{slash}D5{slash}PWM-Pad6)") (class "Default")
      (node (ref "U4") (pin "6") (pinfunction "PD5/D5/PWM_6") (pintype "bidirectional"))
    )
    (net (code "116") (name "unconnected-(U4-PD6{slash}D6{slash}PWM-Pad7)") (class "Default")
      (node (ref "U4") (pin "7") (pinfunction "PD6/D6/PWM_7") (pintype "bidirectional"))
    )
    (net (code "117") (name "unconnected-(U4-RESET-Pad30)") (class "Default")
      (node (ref "U4") (pin "30") (pinfunction "RESET_30") (pintype "bidirectional"))
    )
    (net (code "118") (name "unconnected-(U4-RST-Pad36)") (class "Default")
      (node (ref "U4") (pin "36") (pinfunction "RST_36") (pintype "bidirectional"))
    )
    (net (code "119") (name "unconnected-(U4-SCK-Pad37)") (class "Default")
      (node (ref "U4") (pin "37") (pinfunction "SCK_37") (pintype "bidirectional"))
    )
    (net (code "120") (name "unconnected-(U4-SCL-Pad18)") (class "Default")
      (node (ref "U4") (pin "18") (pinfunction "SCL_18") (pintype "bidirectional"))
    )
    (net (code "121") (name "unconnected-(U4-SDA-Pad17)") (class "Default")
      (node (ref "U4") (pin "17") (pinfunction "SDA_17") (pintype "bidirectional"))
    )
    (net (code "122") (name "unconnected-(U4-VCC-Pad33)") (class "Default")
      (node (ref "U4") (pin "33") (pinfunction "VCC_33") (pintype "bidirectional"))
    )
  )
)
